# Power_SarSol.net
KiCad netlist of a schematic drawn in Altium Designer
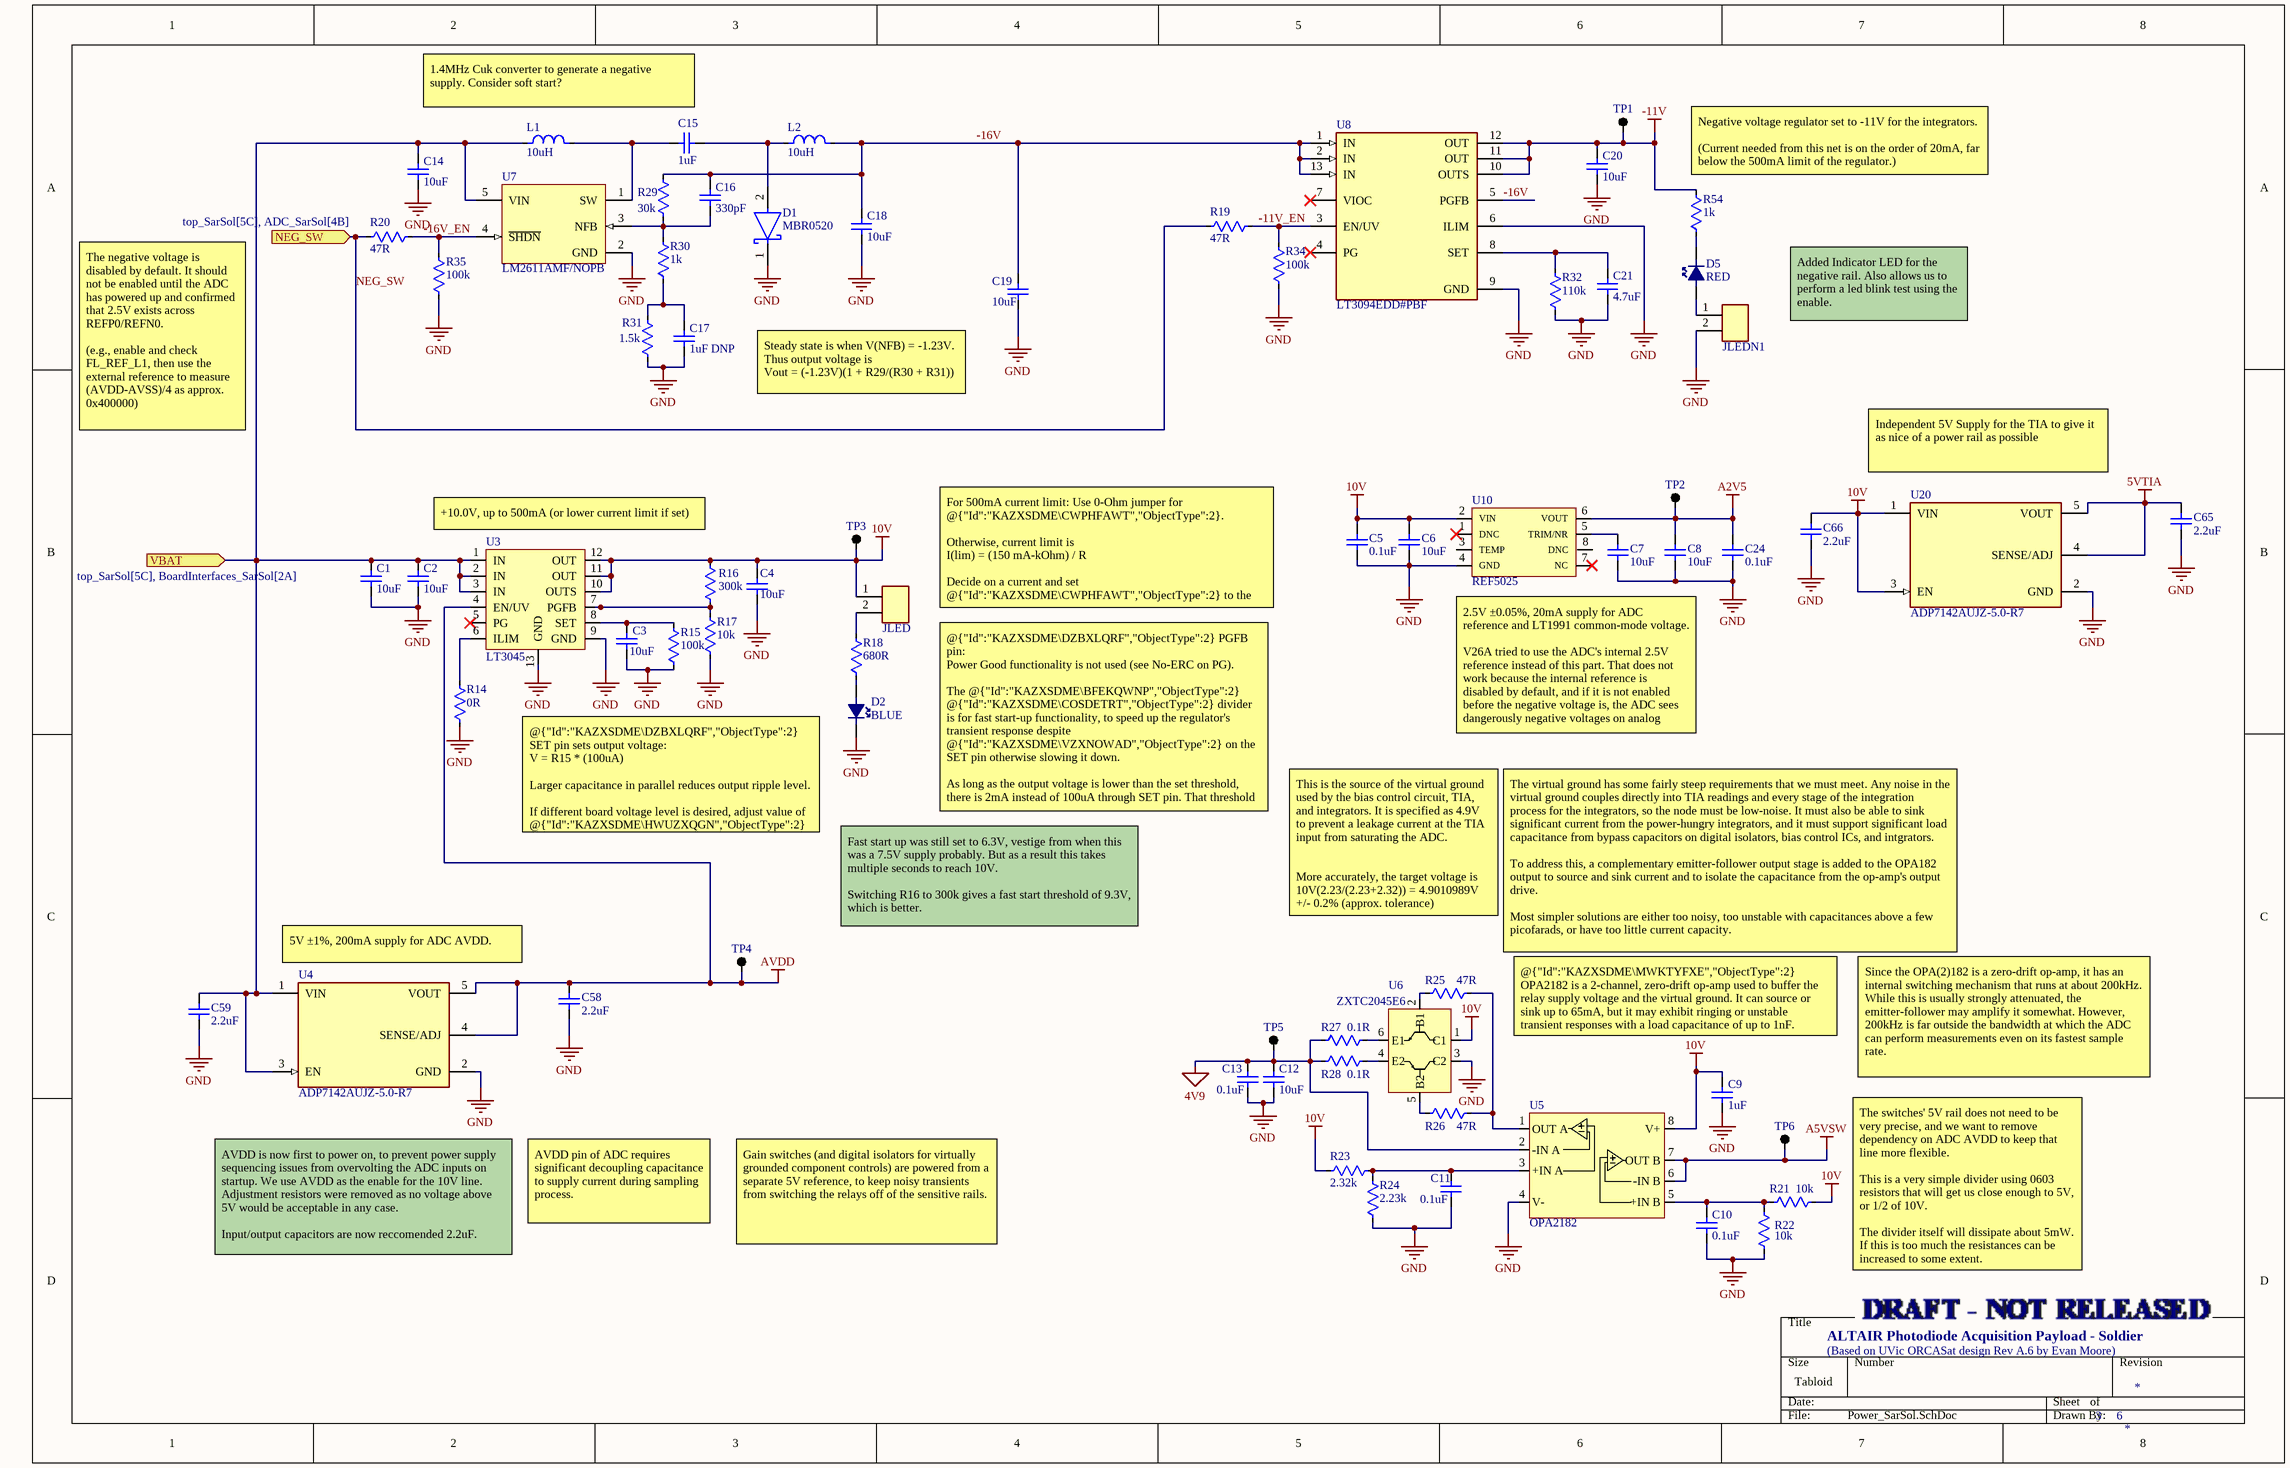
[diagram p0: Power_SarSol.SchDoc]

(export (version "E")
  (design (tool "Eeschema 10.0.6"))
  (components
    (comp (ref "C1")
      (value "10uF")
      (footprint "CAP 1206 IPC LOW DENSITY")
      (description "Murata GRT319R6YA106KE01D - Cap Ceramic 10uF 35V X5R 10% Pad SMD 1206 85C Automotive T/R")
      (fields (field (name "MF") "Murata") (field (name "MP") "GRT319R6YA106KE01D"))
      (libsource (lib "ALTAIR_PD_Capacitors") (part "CAP"))
    )
    (comp (ref "C2")
      (value "10uF")
      (footprint "CAP 1206 IPC LOW DENSITY")
      (description "Murata GRT319R6YA106KE01D - Cap Ceramic 10uF 35V X5R 10% Pad SMD 1206 85C Automotive T/R")
      (fields (field (name "MF") "Murata") (field (name "MP") "GRT319R6YA106KE01D"))
      (libsource (lib "ALTAIR_PD_Capacitors") (part "CAP"))
    )
    (comp (ref "C3")
      (value "10uF")
      (footprint "CAP 1206 IPC LOW DENSITY")
      (description "Murata GRT319R6YA106KE01D - Cap Ceramic 10uF 35V X5R 10% Pad SMD 1206 85C Automotive T/R")
      (fields (field (name "MF") "Murata") (field (name "MP") "GRT319R6YA106KE01D"))
      (libsource (lib "ALTAIR_PD_Capacitors") (part "CAP"))
    )
    (comp (ref "C4")
      (value "10uF")
      (footprint "CAP 1206 IPC LOW DENSITY")
      (description "Murata GRT319R6YA106KE01D - Cap Ceramic 10uF 35V X5R 10% Pad SMD 1206 85C Automotive T/R")
      (fields (field (name "MF") "Murata") (field (name "MP") "GRT319R6YA106KE01D"))
      (libsource (lib "ALTAIR_PD_Capacitors") (part "CAP"))
    )
    (comp (ref "C5")
      (value "0.1uF")
      (footprint "CAP 0603 IPC MID DENSITY")
      (description "Kemet C0603C104K5RACAUTO - Cap Ceramic 0.1uF 50V X7R 10% 0603 125C Paper T/R")
      (fields (field (name "MF") "Kemet") (field (name "MP") "C0603C104K5RACAUTO"))
      (libsource (lib "ALTAIR_PD_Capacitors") (part "CAP"))
    )
    (comp (ref "C6")
      (value "10uF")
      (footprint "CAP 0805 IPC MID DENSITY")
      (description "Murata GRM21BR61E106KA73L - Cap Ceramic 10uF 10% 25V X5R 0805")
      (fields (field (name "MF") "Murata") (field (name "MP") "GRM21BR61E106KA73L"))
      (libsource (lib "ALTAIR_PD_Capacitors") (part "CAP"))
    )
    (comp (ref "C7")
      (value "10uF")
      (footprint "CAP 0805 IPC MID DENSITY")
      (description "Murata GRM21BR61E106KA73L - Cap Ceramic 10uF 10% 25V X5R 0805")
      (fields (field (name "MF") "Murata") (field (name "MP") "GRM21BR61E106KA73L"))
      (libsource (lib "ALTAIR_PD_Capacitors") (part "CAP"))
    )
    (comp (ref "C8")
      (value "10uF")
      (footprint "CAP 0805 IPC MID DENSITY")
      (description "Murata GRM21BR61E106KA73L - Cap Ceramic 10uF 10% 25V X5R 0805")
      (fields (field (name "MF") "Murata") (field (name "MP") "GRM21BR61E106KA73L"))
      (libsource (lib "ALTAIR_PD_Capacitors") (part "CAP"))
    )
    (comp (ref "C9")
      (value "1uF")
      (footprint "CAP 0603 IPC MID DENSITY")
      (description "Murata GRT188R61H105KE13D - Cap MLCC AEC-Q200 X5R 1uF 50V 0603")
      (fields (field (name "MF") "Murata") (field (name "MP") "GRT188R61H105KE13D"))
      (libsource (lib "ALTAIR_PD_Capacitors") (part "CAP"))
    )
    (comp (ref "C10")
      (value "0.1uF")
      (footprint "CAP 0603 IPC MID DENSITY")
      (description "Kemet C0603C104K5RACAUTO - Cap Ceramic 0.1uF 50V X7R 10% 0603 125C Paper T/R")
      (fields (field (name "MF") "Kemet") (field (name "MP") "C0603C104K5RACAUTO"))
      (libsource (lib "ALTAIR_PD_Capacitors") (part "CAP"))
    )
    (comp (ref "C11")
      (value "0.1uF")
      (footprint "CAP 0603 IPC MID DENSITY")
      (description "Kemet C0603C104K5RACAUTO - Cap Ceramic 0.1uF 50V X7R 10% 0603 125C Paper T/R")
      (fields (field (name "MF") "Kemet") (field (name "MP") "C0603C104K5RACAUTO"))
      (libsource (lib "ALTAIR_PD_Capacitors") (part "CAP"))
    )
    (comp (ref "C12")
      (value "10uF")
      (footprint "CAP 1206 IPC LOW DENSITY")
      (description "Murata GRT319R6YA106KE01D - Cap Ceramic 10uF 35V X5R 10% Pad SMD 1206 85C Automotive T/R")
      (fields (field (name "MF") "Murata") (field (name "MP") "GRT319R6YA106KE01D"))
      (libsource (lib "ALTAIR_PD_Capacitors") (part "CAP"))
    )
    (comp (ref "C13")
      (value "0.1uF")
      (footprint "CAP 0603 IPC MID DENSITY")
      (description "Kemet C0603C104K5RACAUTO - Cap Ceramic 0.1uF 50V X7R 10% 0603 125C Paper T/R")
      (fields (field (name "MF") "Kemet") (field (name "MP") "C0603C104K5RACAUTO"))
      (libsource (lib "ALTAIR_PD_Capacitors") (part "CAP"))
    )
    (comp (ref "C14")
      (value "10uF")
      (footprint "CAP 0805 IPC MID DENSITY")
      (description "Murata GRM21BR61E106KA73L - Cap Ceramic 10uF 10% 25V X5R 0805")
      (fields (field (name "MF") "Murata") (field (name "MP") "GRM21BR61E106KA73L"))
      (libsource (lib "ALTAIR_PD_Capacitors") (part "CAP"))
    )
    (comp (ref "C15")
      (value "1uF")
      (footprint "CAP 0603 IPC MID DENSITY")
      (description "Murata GRT188R61H105KE13D - Cap MLCC AEC-Q200 X5R 1uF 50V 0603")
      (fields (field (name "MF") "Murata") (field (name "MP") "GRT188R61H105KE13D"))
      (libsource (lib "ALTAIR_PD_Capacitors") (part "CAP"))
    )
    (comp (ref "C16")
      (value "330pF")
      (footprint "CAP 1206 NON-IPC KEMET NP0")
      (description "Kemet C1206C331J5GACTU - Cap Ceramic 330pF 50V 5% NP0 1206")
      (fields (field (name "MF") "Kemet") (field (name "MP") "C1206C331J5GACTU"))
      (libsource (lib "ALTAIR_PD_Capacitors") (part "CAP"))
    )
    (comp (ref "C17")
      (value "1uF DNP")
      (footprint "CAP 0603 IPC MID DENSITY")
      (description "Murata GRT188R61H105KE13D - Cap MLCC AEC-Q200 X5R 1uF 50V 0603")
      (fields (field (name "MF") "Murata") (field (name "MP") "GRT188R61H105KE13D"))
      (libsource (lib "ALTAIR_PD_Capacitors") (part "CAP"))
    )
    (comp (ref "C18")
      (value "10uF")
      (footprint "CAP 0805 IPC MID DENSITY")
      (description "Murata GRM21BR61E106KA73L - Cap Ceramic 10uF 10% 25V X5R 0805")
      (fields (field (name "MF") "Murata") (field (name "MP") "GRM21BR61E106KA73L"))
      (libsource (lib "ALTAIR_PD_Capacitors") (part "CAP"))
    )
    (comp (ref "C19")
      (value "10uF")
      (footprint "CAP 0805 IPC MID DENSITY")
      (description "Murata GRM21BR61E106KA73L - Cap Ceramic 10uF 10% 25V X5R 0805")
      (fields (field (name "MF") "Murata") (field (name "MP") "GRM21BR61E106KA73L"))
      (libsource (lib "ALTAIR_PD_Capacitors") (part "CAP"))
    )
    (comp (ref "C20")
      (value "10uF")
      (footprint "CAP 0805 IPC MID DENSITY")
      (description "Murata GRM21BR61E106KA73L - Cap Ceramic 10uF 10% 25V X5R 0805")
      (fields (field (name "MF") "Murata") (field (name "MP") "GRM21BR61E106KA73L"))
      (libsource (lib "ALTAIR_PD_Capacitors") (part "CAP"))
    )
    (comp (ref "C21")
      (value "4.7uF")
      (footprint "CAP 0805 NON-IPC KEMET X5R")
      (description "Kemet C0805C475K8PACTU - Cap Ceramic 4.7uF 10V X5R 0805")
      (fields (field (name "MF") "Kemet") (field (name "MP") "C0805C475K8PACTU"))
      (libsource (lib "ALTAIR_PD_Capacitors") (part "CAP"))
    )
    (comp (ref "C24")
      (value "0.1uF")
      (footprint "CAP 0603 IPC MID DENSITY")
      (description "Kemet C0603C104K5RACAUTO - Cap Ceramic 0.1uF 50V X7R 10% 0603 125C Paper T/R")
      (fields (field (name "MF") "Kemet") (field (name "MP") "C0603C104K5RACAUTO"))
      (libsource (lib "ALTAIR_PD_Capacitors") (part "CAP"))
    )
    (comp (ref "C58")
      (value "2.2uF")
      (footprint "CAP 1206 UNKNOWN")
      (description "Cap, Nonpolar, Any, Must choose footprint manually")
      (libsource (lib "ALTAIR_PD_Capacitors") (part "CAP"))
    )
    (comp (ref "C59")
      (value "2.2uF")
      (footprint "CAP 1206 UNKNOWN")
      (description "Cap, Nonpolar, Any, Must choose footprint manually")
      (libsource (lib "ALTAIR_PD_Capacitors") (part "CAP"))
    )
    (comp (ref "C65")
      (value "2.2uF")
      (footprint "CAP 1206 UNKNOWN")
      (description "Cap, Nonpolar, Any, Must choose footprint manually")
      (libsource (lib "ALTAIR_PD_Capacitors") (part "CAP"))
    )
    (comp (ref "C66")
      (value "2.2uF")
      (footprint "CAP 1206 UNKNOWN")
      (description "Cap, Nonpolar, Any, Must choose footprint manually")
      (libsource (lib "ALTAIR_PD_Capacitors") (part "CAP"))
    )
    (comp (ref "D1")
      (value "MBR0520")
      (footprint "SOD-123 ONSEMI SMALL PADS")
      (description "DIODE SCHOTTKY 20V 500MA SOD123")
      (fields (field (name "MF") "onsemi") (field (name "MP") "MBR0520LT1G"))
      (libsource (lib "ALTAIR_PD_Diodes") (part "Schottky"))
    )
    (comp (ref "D2")
      (value "BLUE")
      (footprint "LED 0603 MID DENSITY")
      (description "LED BLUE CLEAR 0603 SMD")
      (fields (field (name "MF") "Wurth Electronics") (field (name "MP") "150060BS75000"))
      (libsource (lib "ALTAIR_PD_Diodes") (part "LED-blue"))
    )
    (comp (ref "D5")
      (value "RED")
      (footprint "LED 0603 MID DENSITY")
      (description "LED BLUE CLEAR 0603 SMD")
      (fields (field (name "MF") "Wurth Electronics") (field (name "MP") "150060BS75000"))
      (libsource (lib "ALTAIR_PD_Diodes") (part "LED-blue"))
    )
    (comp (ref "JLED")
      (value "JLED")
      (footprint "ALTAIR_PD_Headers:JUMPER 2POS 1MM PITCH THT")
      (description "2x1 Header THT 1mm Pitch")
      (fields
        (field (name "MF") "GCT (GLOBAL CONNECTOR TECHNOLOGY)")
        (field (name "MP") "BC020-02-A-0200-0300-L-G")
      )
      (libsource (lib "ALTAIR_PD_Headers") (part "BC020-02-A-0200-0300-L-G"))
    )
    (comp (ref "JLEDN1")
      (value "JLED")
      (footprint "ALTAIR_PD_Headers:JUMPER 2POS 1MM PITCH THT")
      (description "2x1 Header THT 1mm Pitch")
      (fields
        (field (name "MF") "GCT (GLOBAL CONNECTOR TECHNOLOGY)")
        (field (name "MP") "BC020-02-A-0200-0300-L-G")
      )
      (libsource (lib "ALTAIR_PD_Headers") (part "BC020-02-A-0200-0300-L-G"))
    )
    (comp (ref "L1")
      (value "10uH")
      (footprint "IND VLS3012CX-1 NONSTANDARD TDK")
      (description "TDK VLS3012CX-100M-1 - Inductor 10uH 20% 1.25A 0.324Ohm NonstandardPkg")
      (fields (field (name "TOLERANCE") "20%") (field (name "MF") "TDK Corporation"))
      (libsource (lib "ALTAIR_PD_Inductors") (part "IND"))
    )
    (comp (ref "L2")
      (value "10uH")
      (footprint "IND VLS3012CX-1 NONSTANDARD TDK")
      (description "TDK VLS3012CX-100M-1 - Inductor 10uH 20% 1.25A 0.324Ohm NonstandardPkg")
      (fields (field (name "TOLERANCE") "20%") (field (name "MF") "TDK Corporation"))
      (libsource (lib "ALTAIR_PD_Inductors") (part "IND"))
    )
    (comp (ref "R14")
      (value "0R")
      (footprint "RES 0603 IPC MID DENSITY")
      (description "Vishay CRCW06030000Z0EA - Res 0 Ohms 1/8W SMD 0603")
      (fields (field (name "MF") "Vishay Dale") (field (name "MP") "CRCW06030000Z0EA"))
      (libsource (lib "ALTAIR_PD_Resistors") (part "RES"))
    )
    (comp (ref "R15")
      (value "100k")
      (footprint "RES 0603 IPC MID DENSITY")
      (description "Panasonic ERA-3ARB104V - Res SMD 0603 0.1% 0.10W T.C. 10ppm 100K")
      (fields (field (name "MF") "Panasonic Electronic Components") (field (name "MP") "ERA-3ARB104V"))
      (libsource (lib "ALTAIR_PD_Resistors") (part "RES"))
    )
    (comp (ref "R16")
      (value "300k")
      (footprint "RES 0603 IPC MID DENSITY")
      (description "Vishay MCT06030C2003FP500 - Res SMD 200kOhm 1% 1/10W 0603")
      (fields (field (name "MF") "Vishay Dale") (field (name "MP") "MCT06030C2003FP500"))
      (libsource (lib "ALTAIR_PD_Resistors") (part "RES"))
    )
    (comp (ref "R17")
      (value "10k")
      (footprint "RES 0603 IPC MID DENSITY")
      (description "Vishay CRCW060310K0FKEA SMD 0603 10k, CRCW e3 Series, 75V, thick film, 100mW")
      (fields (field (name "MF") "Vishay Dale") (field (name "MP") "CRCW060310K0FKEA"))
      (libsource (lib "ALTAIR_PD_Resistors") (part "RES"))
    )
    (comp (ref "R18")
      (value "680R")
      (footprint "RES 0603 IPC MID DENSITY")
      (description "Panasonic ERJ-3EKF6800V - Res SMD 680 Ohm 1% 1/10W 0603")
      (fields (field (name "MF") "Panasonic Electronic Components") (field (name "MP") "ERJ-3EKF6800V"))
      (libsource (lib "ALTAIR_PD_Resistors") (part "RES"))
    )
    (comp (ref "R19")
      (value "47R")
      (footprint "RES 0603 IPC MID DENSITY")
      (description "Vishay CRCW060347R0JNEA - Res 47Ohm 5% 1/8W SMD 0603")
      (fields (field (name "MF") "Vishay Dale") (field (name "MP") "CRCW060347R0JNEA"))
      (libsource (lib "ALTAIR_PD_Resistors") (part "RES"))
    )
    (comp (ref "R20")
      (value "47R")
      (footprint "RES 0603 IPC MID DENSITY")
      (description "Vishay CRCW060347R0JNEA - Res 47Ohm 5% 1/8W SMD 0603")
      (fields (field (name "MF") "Vishay Dale") (field (name "MP") "CRCW060347R0JNEA"))
      (libsource (lib "ALTAIR_PD_Resistors") (part "RES"))
    )
    (comp (ref "R21")
      (value "10k")
      (footprint "RES 0603 IPC MID DENSITY")
      (description "Vishay CRCW060310K0FKEA SMD 0603 10k, CRCW e3 Series, 75V, thick film, 100mW")
      (fields (field (name "MF") "Vishay Dale") (field (name "MP") "CRCW060310K0FKEA"))
      (libsource (lib "ALTAIR_PD_Resistors") (part "RES"))
    )
    (comp (ref "R22")
      (value "10k")
      (footprint "RES 0603 IPC MID DENSITY")
      (description "Vishay CRCW060310K0FKEA SMD 0603 10k, CRCW e3 Series, 75V, thick film, 100mW")
      (fields (field (name "MF") "Vishay Dale") (field (name "MP") "CRCW060310K0FKEA"))
      (libsource (lib "ALTAIR_PD_Resistors") (part "RES"))
    )
    (comp (ref "R23")
      (value "2.32k")
      (footprint "RES 0603 IPC MID DENSITY")
      (description "Vishay TNPW06032K32BEEA - Res 2.32k 0.1% 0.21W SMD 0603")
      (fields (field (name "MF") "Vishay Dale") (field (name "MP") "TNPW06032K32BEEA"))
      (libsource (lib "ALTAIR_PD_Resistors") (part "RES"))
    )
    (comp (ref "R24")
      (value "2.23k")
      (footprint "RES 0603 IPC MID DENSITY")
      (description "KOA Speer RN73R1JTTD2231B25 - Res 2.23k 0.1% 1/10W SMD 0603")
      (fields (field (name "MF") "KOA Speer Electronics, Inc.") (field (name "MP") "RN73R1JTTD2231B25"))
      (libsource (lib "ALTAIR_PD_Resistors") (part "RES"))
    )
    (comp (ref "R25")
      (value "47R")
      (footprint "RES 0402 NON-IPC SEI")
      (description "Stackpole RMCF0402JT47R0 - Res 47Ohm 5% 0.063W 0402 Thick Film AEC-Q200 compliant")
      (fields (field (name "MF") "Stackpole Electronics Inc.") (field (name "MP") "RMCF0402JT47R0"))
      (libsource (lib "ALTAIR_PD_Resistors") (part "RES"))
    )
    (comp (ref "R26")
      (value "47R")
      (footprint "RES 0402 NON-IPC SEI")
      (description "Stackpole RMCF0402JT47R0 - Res 47Ohm 5% 0.063W 0402 Thick Film AEC-Q200 compliant")
      (fields (field (name "MF") "Stackpole Electronics Inc.") (field (name "MP") "RMCF0402JT47R0"))
      (libsource (lib "ALTAIR_PD_Resistors") (part "RES"))
    )
    (comp (ref "R27")
      (value "0.1R")
      (footprint "RES 0402 NON-IPC YAGEO")
      (description "Yageo RL0402JR-070R1L - Res 0.1Ohm 5% 1/16W SMD 0402")
      (fields (field (name "MF") "YAGEO") (field (name "MP") "RL0402JR-070R1L"))
      (libsource (lib "ALTAIR_PD_Resistors") (part "RES"))
    )
    (comp (ref "R28")
      (value "0.1R")
      (footprint "RES 0402 NON-IPC YAGEO")
      (description "Yageo RL0402JR-070R1L - Res 0.1Ohm 5% 1/16W SMD 0402")
      (fields (field (name "MF") "YAGEO") (field (name "MP") "RL0402JR-070R1L"))
      (libsource (lib "ALTAIR_PD_Resistors") (part "RES"))
    )
    (comp (ref "R29")
      (value "30k")
      (footprint "RES 0805 IPC HIGH DENSITY")
      (description "Panasonic ERA-6AEB303V - Res 30kOhm 0.1% 1/8W 0805")
      (fields (field (name "MF") "Panasonic Electronic Components") (field (name "MP") "ERA-6AEB303V"))
      (libsource (lib "ALTAIR_PD_Resistors") (part "RES"))
    )
    (comp (ref "R30")
      (value "1k")
      (footprint "RES 0402 IPC LOW DENSITY YAGEO")
      (description "Yageo RC0402FR-071KL - Res 1kOhm 1% 1/16W 0402")
      (fields (field (name "MF") "YAGEO") (field (name "MP") "RC0402FR-071KL"))
      (libsource (lib "ALTAIR_PD_Resistors") (part "RES"))
    )
    (comp (ref "R31")
      (value "1.5k")
      (footprint "RES 1206 NON-IPC VISHAY")
      (description "Vishay TNPU12061K50BZEN00 - Res 1.5kOhm 0.1% 1/4W 1206")
      (fields (field (name "MF") "Vishay Dale") (field (name "MP") "TNPU12061K50BZEN00"))
      (libsource (lib "ALTAIR_PD_Resistors") (part "RES"))
    )
    (comp (ref "R32")
      (value "110k")
      (footprint "RES 0603 IPC MID DENSITY")
      (description "Panasonic ERA-3AEB114V - Res 110k 0.1% 1/10W SMD 0603")
      (fields (field (name "MF") "Panasonic Electronic Components") (field (name "MP") "ERA-3AEB114V"))
      (libsource (lib "ALTAIR_PD_Resistors") (part "RES"))
    )
    (comp (ref "R34")
      (value "100k")
      (footprint "RES 0603 IPC MID DENSITY")
      (description "Panasonic ERJ-3GEYJ104V - Res 100k 5% 1/10W SMD 0603")
      (fields (field (name "MF") "Panasonic Electronic Components") (field (name "MP") "ERJ-3GEYJ104V"))
      (libsource (lib "ALTAIR_PD_Resistors") (part "RES"))
    )
    (comp (ref "R35")
      (value "100k")
      (footprint "RES 0603 IPC MID DENSITY")
      (description "Panasonic ERJ-3GEYJ104V - Res 100k 5% 1/10W SMD 0603")
      (fields (field (name "MF") "Panasonic Electronic Components") (field (name "MP") "ERJ-3GEYJ104V"))
      (libsource (lib "ALTAIR_PD_Resistors") (part "RES"))
    )
    (comp (ref "R54")
      (value "1k")
      (footprint "RES 0603 IPC MID DENSITY")
      (description "Panasonic ERJ-3EKF6800V - Res SMD 680 Ohm 1% 1/10W 0603")
      (fields (field (name "MF") "Panasonic Electronic Components") (field (name "MP") "ERJ-3EKF6800V"))
      (libsource (lib "ALTAIR_PD_Resistors") (part "RES"))
    )
    (comp (ref "TP1")
      (value "Testpoint")
      (footprint "TESTPOINT THT")
      (libsource (lib "ALTAIR_PD_Testpoint") (part "Testpoint"))
    )
    (comp (ref "TP2")
      (value "Testpoint")
      (footprint "TESTPOINT THT")
      (libsource (lib "ALTAIR_PD_Testpoint") (part "Testpoint"))
    )
    (comp (ref "TP3")
      (value "Testpoint")
      (footprint "TESTPOINT THT")
      (libsource (lib "ALTAIR_PD_Testpoint") (part "Testpoint"))
    )
    (comp (ref "TP4")
      (value "Testpoint")
      (footprint "TESTPOINT THT")
      (libsource (lib "ALTAIR_PD_Testpoint") (part "Testpoint"))
    )
    (comp (ref "TP5")
      (value "Testpoint")
      (footprint "TESTPOINT THT")
      (libsource (lib "ALTAIR_PD_Testpoint") (part "Testpoint"))
    )
    (comp (ref "TP6")
      (value "Testpoint")
      (footprint "TESTPOINT THT")
      (libsource (lib "ALTAIR_PD_Testpoint") (part "Testpoint"))
    )
    (comp (ref "U3")
      (value "LT3045")
      (footprint "12-TSOP 0.65MM PITCH 3MM WIDTH EP IPC MID DENSITY")
      (description "20V 500mA Ultralow Noise Ultrahigh PSRR Adjustable Linear Regulator 260V Dropout MSOP-12")
      (fields (field (name "MF") "Analog Devices / Linear Technology") (field (name "MP") "LT3045EMSE#PBF"))
      (libsource (lib "ALTAIR_PD_Regulators") (part "LT3045"))
    )
    (comp (ref "U4")
      (value "ADP7142AUJZ-5.0-R7")
      (footprint "SOT23-5 HIGH DENSITY AD")
      (description "1.2-40V 200mA Low Noise CMOS LDO Adjustable Linear Regulator TSOT23")
      (fields
        (field (name "OCTOPART") "https://octopart.com/adp7142aujz-r7-analog+devices-38928114")
        (field (name "MF") "Analog Devices")
      )
      (libsource (lib "ALTAIR_PD_Regulators") (part "ADP7142AUJZ-R7"))
    )
    (comp (ref "U5")
      (value "OPA2182")
      (footprint "8-TSSOP 0.65MM PITCH 4.4MM WIDTH IPC MID DENSITY")
      (fields (field (name "MF") "Texas Instruments") (field (name "MP") "OPA2182IDGKR"))
      (libsource (lib "ALTAIR_PD_Amplifiers") (part "OPA2182IDBV"))
    )
    (comp (ref "U6")
      (value "ZXTC2045E6")
      (footprint "SOT23-6 NON-IPC DIODES")
      (description "BJT Array, 1NPN 1PNP, VCE(sat) 375mV, hFE 300, Breakdown 30V, 6-SOT-23")
      (fields (field (name "MF") "Diodes Incorporated") (field (name "MP") "ZXTC2045E6TA"))
      (libsource (lib "ALTAIR_PD_BJTs") (part "ZXTC2045E6"))
    )
    (comp (ref "U7")
      (value "LM2611AMF/NOPB")
      (footprint "SOT23-5 MID DENSITY")
      (description "1.4MHz Cuk Converter, 5-pin SOT-23, Pb-Free")
      (fields (field (name "MF") "Texas Instruments"))
      (libsource (lib "ALTAIR_PD_Converters") (part "LM2611AMF"))
    )
    (comp (ref "U8")
      (value "LT3094EDD#PBF")
      (footprint "12DFN 3x3MM EP IPC MID DENSITY")
      (description "-20V 500mA Ultralow Noise Ultrahigh PSRR Adjustable Negative Linear Regulator 12DFN")
      (fields (field (name "MF") "Analog Devices"))
      (libsource (lib "ALTAIR_PD_Regulators") (part "LT3094EDD#PBF"))
    )
    (comp (ref "U10")
      (value "REF5025")
      (footprint "8-TSOP 0.65MM PITCH 3MM WIDTH IPC MID DENSITY")
      (description "2.5V±0.05% Voltage Reference 8VSSOP")
      (fields (field (name "MF") "Texas Instruments") (field (name "MP") "REF5025IDGKR"))
      (libsource (lib "ALTAIR_PD_MiscPower") (part "REF5050IDGKR"))
    )
    (comp (ref "U20")
      (value "ADP7142AUJZ-5.0-R7")
      (footprint "SOT23-5 HIGH DENSITY AD")
      (description "1.2-40V 200mA Low Noise CMOS LDO Adjustable Linear Regulator TSOT23")
      (fields
        (field (name "OCTOPART") "https://octopart.com/adp7142aujz-r7-analog+devices-38928114")
        (field (name "MF") "Analog Devices")
      )
      (libsource (lib "ALTAIR_PD_Regulators") (part "ADP7142AUJZ-R7"))
    )
  )
  (nets
    (net (code "1") (name "-11V") (class "Default")
      (node (ref "C20") (pin "1") (pinfunction "1_1") (pintype "passive"))
      (node (ref "R54") (pin "2") (pinfunction "2_2") (pintype "passive"))
      (node (ref "TP1") (pin "1") (pinfunction "1_1") (pintype "passive"))
      (node (ref "U8") (pin "10") (pinfunction "OUTS_10") (pintype "power_in"))
      (node (ref "U8") (pin "11") (pinfunction "OUT_11") (pintype "power_in"))
      (node (ref "U8") (pin "12") (pinfunction "OUT_12") (pintype "power_in"))
    )
    (net (code "2") (name "/-11V_EN") (class "Default")
      (node (ref "R19") (pin "1") (pinfunction "1_1") (pintype "passive"))
      (node (ref "R34") (pin "1") (pinfunction "1_1") (pintype "passive"))
      (node (ref "U8") (pin "3") (pinfunction "EN/UV_3") (pintype "passive"))
    )
    (net (code "3") (name "/-16V") (class "Default")
      (node (ref "C16") (pin "1") (pinfunction "1_1") (pintype "passive"))
      (node (ref "C18") (pin "1") (pinfunction "1_1") (pintype "passive"))
      (node (ref "C19") (pin "1") (pinfunction "1_1") (pintype "passive"))
      (node (ref "L2") (pin "2") (pinfunction "2_2") (pintype "passive"))
      (node (ref "R29") (pin "2") (pinfunction "2_2") (pintype "passive"))
      (node (ref "U8") (pin "1") (pinfunction "IN_1") (pintype "input"))
      (node (ref "U8") (pin "13") (pinfunction "IN_13") (pintype "input"))
      (node (ref "U8") (pin "2") (pinfunction "IN_2") (pintype "input"))
      (node (ref "U8") (pin "5") (pinfunction "PGFB_5") (pintype "passive"))
    )
    (net (code "4") (name "/-16V_EN") (class "Default")
      (node (ref "R20") (pin "1") (pinfunction "1_1") (pintype "passive"))
      (node (ref "R35") (pin "1") (pinfunction "1_1") (pintype "passive"))
      (node (ref "U7") (pin "4") (pinfunction "~{SHDN}_4") (pintype "input"))
    )
    (net (code "5") (name "/NEG_SW") (class "Default")
      (node (ref "R19") (pin "2") (pinfunction "2_2") (pintype "passive"))
      (node (ref "R20") (pin "2") (pinfunction "2_2") (pintype "passive"))
    )
    (net (code "6") (name "/VBAT") (class "Default")
      (node (ref "C1") (pin "2") (pinfunction "2_2") (pintype "passive"))
      (node (ref "C14") (pin "2") (pinfunction "2_2") (pintype "passive"))
      (node (ref "C2") (pin "2") (pinfunction "2_2") (pintype "passive"))
      (node (ref "C59") (pin "1") (pinfunction "1_1") (pintype "passive"))
      (node (ref "L1") (pin "1") (pinfunction "1_1") (pintype "passive"))
      (node (ref "U3") (pin "1") (pinfunction "IN_1") (pintype "passive"))
      (node (ref "U3") (pin "2") (pinfunction "IN_2") (pintype "passive"))
      (node (ref "U3") (pin "3") (pinfunction "IN_3") (pintype "passive"))
      (node (ref "U4") (pin "1") (pinfunction "VIN_1") (pintype "power_in"))
      (node (ref "U4") (pin "3") (pinfunction "EN_3") (pintype "input"))
      (node (ref "U7") (pin "5") (pinfunction "VIN_5") (pintype "power_in"))
    )
    (net (code "7") (name "4V9") (class "Default")
      (node (ref "C12") (pin "2") (pinfunction "2_2") (pintype "passive"))
      (node (ref "C13") (pin "2") (pinfunction "2_2") (pintype "passive"))
      (node (ref "R27") (pin "1") (pinfunction "1_1") (pintype "passive"))
      (node (ref "R28") (pin "1") (pinfunction "1_1") (pintype "passive"))
      (node (ref "TP5") (pin "1") (pinfunction "1_1") (pintype "passive"))
      (node (ref "U5") (pin "2") (pinfunction "-IN_A_2") (pintype "passive"))
    )
    (net (code "8") (name "5VTIA") (class "Default")
      (node (ref "C65") (pin "1") (pinfunction "1_1") (pintype "passive"))
      (node (ref "U20") (pin "4") (pinfunction "SENSE/ADJ_4") (pintype "passive"))
      (node (ref "U20") (pin "5") (pinfunction "VOUT_5") (pintype "passive"))
    )
    (net (code "9") (name "10V") (class "Default")
      (node (ref "C4") (pin "2") (pinfunction "2_2") (pintype "passive"))
      (node (ref "C5") (pin "1") (pinfunction "1_1") (pintype "passive"))
      (node (ref "C6") (pin "2") (pinfunction "2_2") (pintype "passive"))
      (node (ref "C66") (pin "1") (pinfunction "1_1") (pintype "passive"))
      (node (ref "C9") (pin "2") (pinfunction "2_2") (pintype "passive"))
      (node (ref "JLED") (pin "1") (pinfunction "1_1") (pintype "passive"))
      (node (ref "R16") (pin "2") (pinfunction "2_2") (pintype "passive"))
      (node (ref "R21") (pin "2") (pinfunction "2_2") (pintype "passive"))
      (node (ref "R23") (pin "2") (pinfunction "2_2") (pintype "passive"))
      (node (ref "TP3") (pin "1") (pinfunction "1_1") (pintype "passive"))
      (node (ref "U10") (pin "2") (pinfunction "VIN_2") (pintype "passive"))
      (node (ref "U20") (pin "1") (pinfunction "VIN_1") (pintype "power_in"))
      (node (ref "U20") (pin "3") (pinfunction "EN_3") (pintype "input"))
      (node (ref "U3") (pin "10") (pinfunction "OUTS_10") (pintype "passive"))
      (node (ref "U3") (pin "11") (pinfunction "OUT_11") (pintype "passive"))
      (node (ref "U3") (pin "12") (pinfunction "OUT_12") (pintype "passive"))
      (node (ref "U5") (pin "8") (pinfunction "V+_8") (pintype "passive"))
      (node (ref "U6") (pin "1") (pinfunction "C1_1") (pintype "passive"))
    )
    (net (code "10") (name "A2V5") (class "Default")
      (node (ref "C24") (pin "1") (pinfunction "1_1") (pintype "passive"))
      (node (ref "C8") (pin "2") (pinfunction "2_2") (pintype "passive"))
      (node (ref "TP2") (pin "1") (pinfunction "1_1") (pintype "passive"))
      (node (ref "U10") (pin "6") (pinfunction "VOUT_6") (pintype "passive"))
    )
    (net (code "11") (name "A5VSW") (class "Default")
      (node (ref "TP6") (pin "1") (pinfunction "1_1") (pintype "passive"))
      (node (ref "U5") (pin "6") (pinfunction "-IN_B_6") (pintype "passive"))
      (node (ref "U5") (pin "7") (pinfunction "OUT_B_7") (pintype "passive"))
    )
    (net (code "12") (name "AVDD") (class "Default")
      (node (ref "C58") (pin "1") (pinfunction "1_1") (pintype "passive"))
      (node (ref "TP4") (pin "1") (pinfunction "1_1") (pintype "passive"))
      (node (ref "U3") (pin "4") (pinfunction "EN/UV_4") (pintype "passive"))
      (node (ref "U4") (pin "4") (pinfunction "SENSE/ADJ_4") (pintype "passive"))
      (node (ref "U4") (pin "5") (pinfunction "VOUT_5") (pintype "passive"))
    )
    (net (code "13") (name "GND") (class "Default")
      (node (ref "C1") (pin "1") (pinfunction "1_1") (pintype "passive"))
      (node (ref "C10") (pin "1") (pinfunction "1_1") (pintype "passive"))
      (node (ref "C11") (pin "1") (pinfunction "1_1") (pintype "passive"))
      (node (ref "C12") (pin "1") (pinfunction "1_1") (pintype "passive"))
      (node (ref "C13") (pin "1") (pinfunction "1_1") (pintype "passive"))
      (node (ref "C14") (pin "1") (pinfunction "1_1") (pintype "passive"))
      (node (ref "C17") (pin "2") (pinfunction "2_2") (pintype "passive"))
      (node (ref "C18") (pin "2") (pinfunction "2_2") (pintype "passive"))
      (node (ref "C19") (pin "2") (pinfunction "2_2") (pintype "passive"))
      (node (ref "C2") (pin "1") (pinfunction "1_1") (pintype "passive"))
      (node (ref "C20") (pin "2") (pinfunction "2_2") (pintype "passive"))
      (node (ref "C21") (pin "2") (pinfunction "2_2") (pintype "passive"))
      (node (ref "C24") (pin "2") (pinfunction "2_2") (pintype "passive"))
      (node (ref "C3") (pin "1") (pinfunction "1_1") (pintype "passive"))
      (node (ref "C4") (pin "1") (pinfunction "1_1") (pintype "passive"))
      (node (ref "C5") (pin "2") (pinfunction "2_2") (pintype "passive"))
      (node (ref "C58") (pin "2") (pinfunction "2_2") (pintype "passive"))
      (node (ref "C59") (pin "2") (pinfunction "2_2") (pintype "passive"))
      (node (ref "C6") (pin "1") (pinfunction "1_1") (pintype "passive"))
      (node (ref "C65") (pin "2") (pinfunction "2_2") (pintype "passive"))
      (node (ref "C66") (pin "2") (pinfunction "2_2") (pintype "passive"))
      (node (ref "C7") (pin "2") (pinfunction "2_2") (pintype "passive"))
      (node (ref "C8") (pin "1") (pinfunction "1_1") (pintype "passive"))
      (node (ref "C9") (pin "1") (pinfunction "1_1") (pintype "passive"))
      (node (ref "D1") (pin "1") (pinfunction "C_1") (pintype "passive"))
      (node (ref "D2") (pin "1") (pinfunction "1_1") (pintype "passive"))
      (node (ref "JLEDN1") (pin "2") (pinfunction "2_2") (pintype "passive"))
      (node (ref "R14") (pin "1") (pinfunction "1_1") (pintype "passive"))
      (node (ref "R15") (pin "1") (pinfunction "1_1") (pintype "passive"))
      (node (ref "R17") (pin "1") (pinfunction "1_1") (pintype "passive"))
      (node (ref "R22") (pin "1") (pinfunction "1_1") (pintype "passive"))
      (node (ref "R24") (pin "1") (pinfunction "1_1") (pintype "passive"))
      (node (ref "R31") (pin "1") (pinfunction "1_1") (pintype "passive"))
      (node (ref "R32") (pin "2") (pinfunction "2_2") (pintype "passive"))
      (node (ref "R34") (pin "2") (pinfunction "2_2") (pintype "passive"))
      (node (ref "R35") (pin "2") (pinfunction "2_2") (pintype "passive"))
      (node (ref "U10") (pin "4") (pinfunction "GND_4") (pintype "passive"))
      (node (ref "U20") (pin "2") (pinfunction "GND_2") (pintype "power_in"))
      (node (ref "U3") (pin "13") (pinfunction "GND_13") (pintype "passive"))
      (node (ref "U3") (pin "9") (pinfunction "GND_9") (pintype "passive"))
      (node (ref "U4") (pin "2") (pinfunction "GND_2") (pintype "power_in"))
      (node (ref "U5") (pin "4") (pinfunction "V-_4") (pintype "passive"))
      (node (ref "U6") (pin "3") (pinfunction "C2_3") (pintype "passive"))
      (node (ref "U7") (pin "2") (pinfunction "GND_2") (pintype "power_in"))
      (node (ref "U8") (pin "6") (pinfunction "ILIM_6") (pintype "passive"))
      (node (ref "U8") (pin "9") (pinfunction "GND_9") (pintype "power_in"))
    )
    (net (code "14") (name "Net-(C17-Pad1)") (class "Default")
      (node (ref "C17") (pin "1") (pinfunction "1_1") (pintype "passive"))
      (node (ref "R30") (pin "1") (pinfunction "1_1") (pintype "passive"))
      (node (ref "R31") (pin "2") (pinfunction "2_2") (pintype "passive"))
    )
    (net (code "15") (name "Net-(D1-A)") (class "Default")
      (node (ref "C15") (pin "2") (pinfunction "2_2") (pintype "passive"))
      (node (ref "D1") (pin "2") (pinfunction "A_2") (pintype "passive"))
      (node (ref "L2") (pin "1") (pinfunction "1_1") (pintype "passive"))
    )
    (net (code "16") (name "Net-(D2-Pad2)") (class "Default")
      (node (ref "D2") (pin "2") (pinfunction "2_2") (pintype "passive"))
      (node (ref "R18") (pin "1") (pinfunction "1_1") (pintype "passive"))
    )
    (net (code "17") (name "Net-(D5-Pad1)") (class "Default")
      (node (ref "D5") (pin "1") (pinfunction "1_1") (pintype "passive"))
      (node (ref "R54") (pin "1") (pinfunction "1_1") (pintype "passive"))
    )
    (net (code "18") (name "Net-(D5-Pad2)") (class "Default")
      (node (ref "D5") (pin "2") (pinfunction "2_2") (pintype "passive"))
      (node (ref "JLEDN1") (pin "1") (pinfunction "1_1") (pintype "passive"))
    )
    (net (code "19") (name "Net-(JLED-Pad2)") (class "Default")
      (node (ref "JLED") (pin "2") (pinfunction "2_2") (pintype "passive"))
      (node (ref "R18") (pin "2") (pinfunction "2_2") (pintype "passive"))
    )
    (net (code "20") (name "Net-(U3-ILIM)") (class "Default")
      (node (ref "R14") (pin "2") (pinfunction "2_2") (pintype "passive"))
      (node (ref "U3") (pin "6") (pinfunction "ILIM_6") (pintype "passive"))
    )
    (net (code "21") (name "Net-(U3-PGFB)") (class "Default")
      (node (ref "R16") (pin "1") (pinfunction "1_1") (pintype "passive"))
      (node (ref "R17") (pin "2") (pinfunction "2_2") (pintype "passive"))
      (node (ref "U3") (pin "7") (pinfunction "PGFB_7") (pintype "passive"))
    )
    (net (code "22") (name "Net-(U3-SET)") (class "Default")
      (node (ref "C3") (pin "2") (pinfunction "2_2") (pintype "passive"))
      (node (ref "R15") (pin "2") (pinfunction "2_2") (pintype "passive"))
      (node (ref "U3") (pin "8") (pinfunction "SET_8") (pintype "passive"))
    )
    (net (code "23") (name "Net-(U5-+IN_A)") (class "Default")
      (node (ref "C11") (pin "2") (pinfunction "2_2") (pintype "passive"))
      (node (ref "R23") (pin "1") (pinfunction "1_1") (pintype "passive"))
      (node (ref "R24") (pin "2") (pinfunction "2_2") (pintype "passive"))
      (node (ref "U5") (pin "3") (pinfunction "+IN_A_3") (pintype "passive"))
    )
    (net (code "24") (name "Net-(U5-+IN_B)") (class "Default")
      (node (ref "C10") (pin "2") (pinfunction "2_2") (pintype "passive"))
      (node (ref "R21") (pin "1") (pinfunction "1_1") (pintype "passive"))
      (node (ref "R22") (pin "2") (pinfunction "2_2") (pintype "passive"))
      (node (ref "U5") (pin "5") (pinfunction "+IN_B_5") (pintype "passive"))
    )
    (net (code "25") (name "Net-(U5-OUT_A)") (class "Default")
      (node (ref "R25") (pin "2") (pinfunction "2_2") (pintype "passive"))
      (node (ref "R26") (pin "2") (pinfunction "2_2") (pintype "passive"))
      (node (ref "U5") (pin "1") (pinfunction "OUT_A_1") (pintype "passive"))
    )
    (net (code "26") (name "Net-(U6-B1)") (class "Default")
      (node (ref "R25") (pin "1") (pinfunction "1_1") (pintype "passive"))
      (node (ref "U6") (pin "2") (pinfunction "B1_2") (pintype "passive"))
    )
    (net (code "27") (name "Net-(U6-B2)") (class "Default")
      (node (ref "R26") (pin "1") (pinfunction "1_1") (pintype "passive"))
      (node (ref "U6") (pin "5") (pinfunction "B2_5") (pintype "passive"))
    )
    (net (code "28") (name "Net-(U6-E1)") (class "Default")
      (node (ref "R27") (pin "2") (pinfunction "2_2") (pintype "passive"))
      (node (ref "U6") (pin "6") (pinfunction "E1_6") (pintype "passive"))
    )
    (net (code "29") (name "Net-(U6-E2)") (class "Default")
      (node (ref "R28") (pin "2") (pinfunction "2_2") (pintype "passive"))
      (node (ref "U6") (pin "4") (pinfunction "E2_4") (pintype "passive"))
    )
    (net (code "30") (name "Net-(U7-NFB)") (class "Default")
      (node (ref "C16") (pin "2") (pinfunction "2_2") (pintype "passive"))
      (node (ref "R29") (pin "1") (pinfunction "1_1") (pintype "passive"))
      (node (ref "R30") (pin "2") (pinfunction "2_2") (pintype "passive"))
      (node (ref "U7") (pin "3") (pinfunction "NFB_3") (pintype "input"))
    )
    (net (code "31") (name "Net-(U7-SW)") (class "Default")
      (node (ref "C15") (pin "1") (pinfunction "1_1") (pintype "passive"))
      (node (ref "L1") (pin "2") (pinfunction "2_2") (pintype "passive"))
      (node (ref "U7") (pin "1") (pinfunction "SW_1") (pintype "power_in"))
    )
    (net (code "32") (name "Net-(U8-SET)") (class "Default")
      (node (ref "C21") (pin "1") (pinfunction "1_1") (pintype "passive"))
      (node (ref "R32") (pin "1") (pinfunction "1_1") (pintype "passive"))
      (node (ref "U8") (pin "8") (pinfunction "SET_8") (pintype "passive"))
    )
    (net (code "33") (name "Net-(U10-TRIM{slash}NR)") (class "Default")
      (node (ref "C7") (pin "1") (pinfunction "1_1") (pintype "passive"))
      (node (ref "U10") (pin "5") (pinfunction "TRIM/NR_5") (pintype "passive"))
    )
    (net (code "34") (name "unconnected-(U3-PG-Pad5)") (class "Default")
      (node (ref "U3") (pin "5") (pinfunction "PG_5") (pintype "passive+no_connect"))
    )
    (net (code "35") (name "unconnected-(U8-PG-Pad4)") (class "Default")
      (node (ref "U8") (pin "4") (pinfunction "PG_4") (pintype "passive+no_connect"))
    )
    (net (code "36") (name "unconnected-(U8-VIOC-Pad7)") (class "Default")
      (node (ref "U8") (pin "7") (pinfunction "VIOC_7") (pintype "passive+no_connect"))
    )
    (net (code "37") (name "unconnected-(U10-DNC-Pad1)") (class "Default")
      (node (ref "U10") (pin "1") (pinfunction "DNC_1") (pintype "passive+no_connect"))
    )
    (net (code "38") (name "unconnected-(U10-DNC-Pad8)") (class "Default")
      (node (ref "U10") (pin "8") (pinfunction "DNC_8") (pintype "passive"))
    )
    (net (code "39") (name "unconnected-(U10-NC-Pad7)") (class "Default")
      (node (ref "U10") (pin "7") (pinfunction "NC_7") (pintype "passive+no_connect"))
    )
    (net (code "40") (name "unconnected-(U10-TEMP-Pad3)") (class "Default")
      (node (ref "U10") (pin "3") (pinfunction "TEMP_3") (pintype "passive"))
    )
  )
)
